# ProPrj__ByByte_Nano.net
KiCad netlist of a schematic drawn in EasyEDA Pro
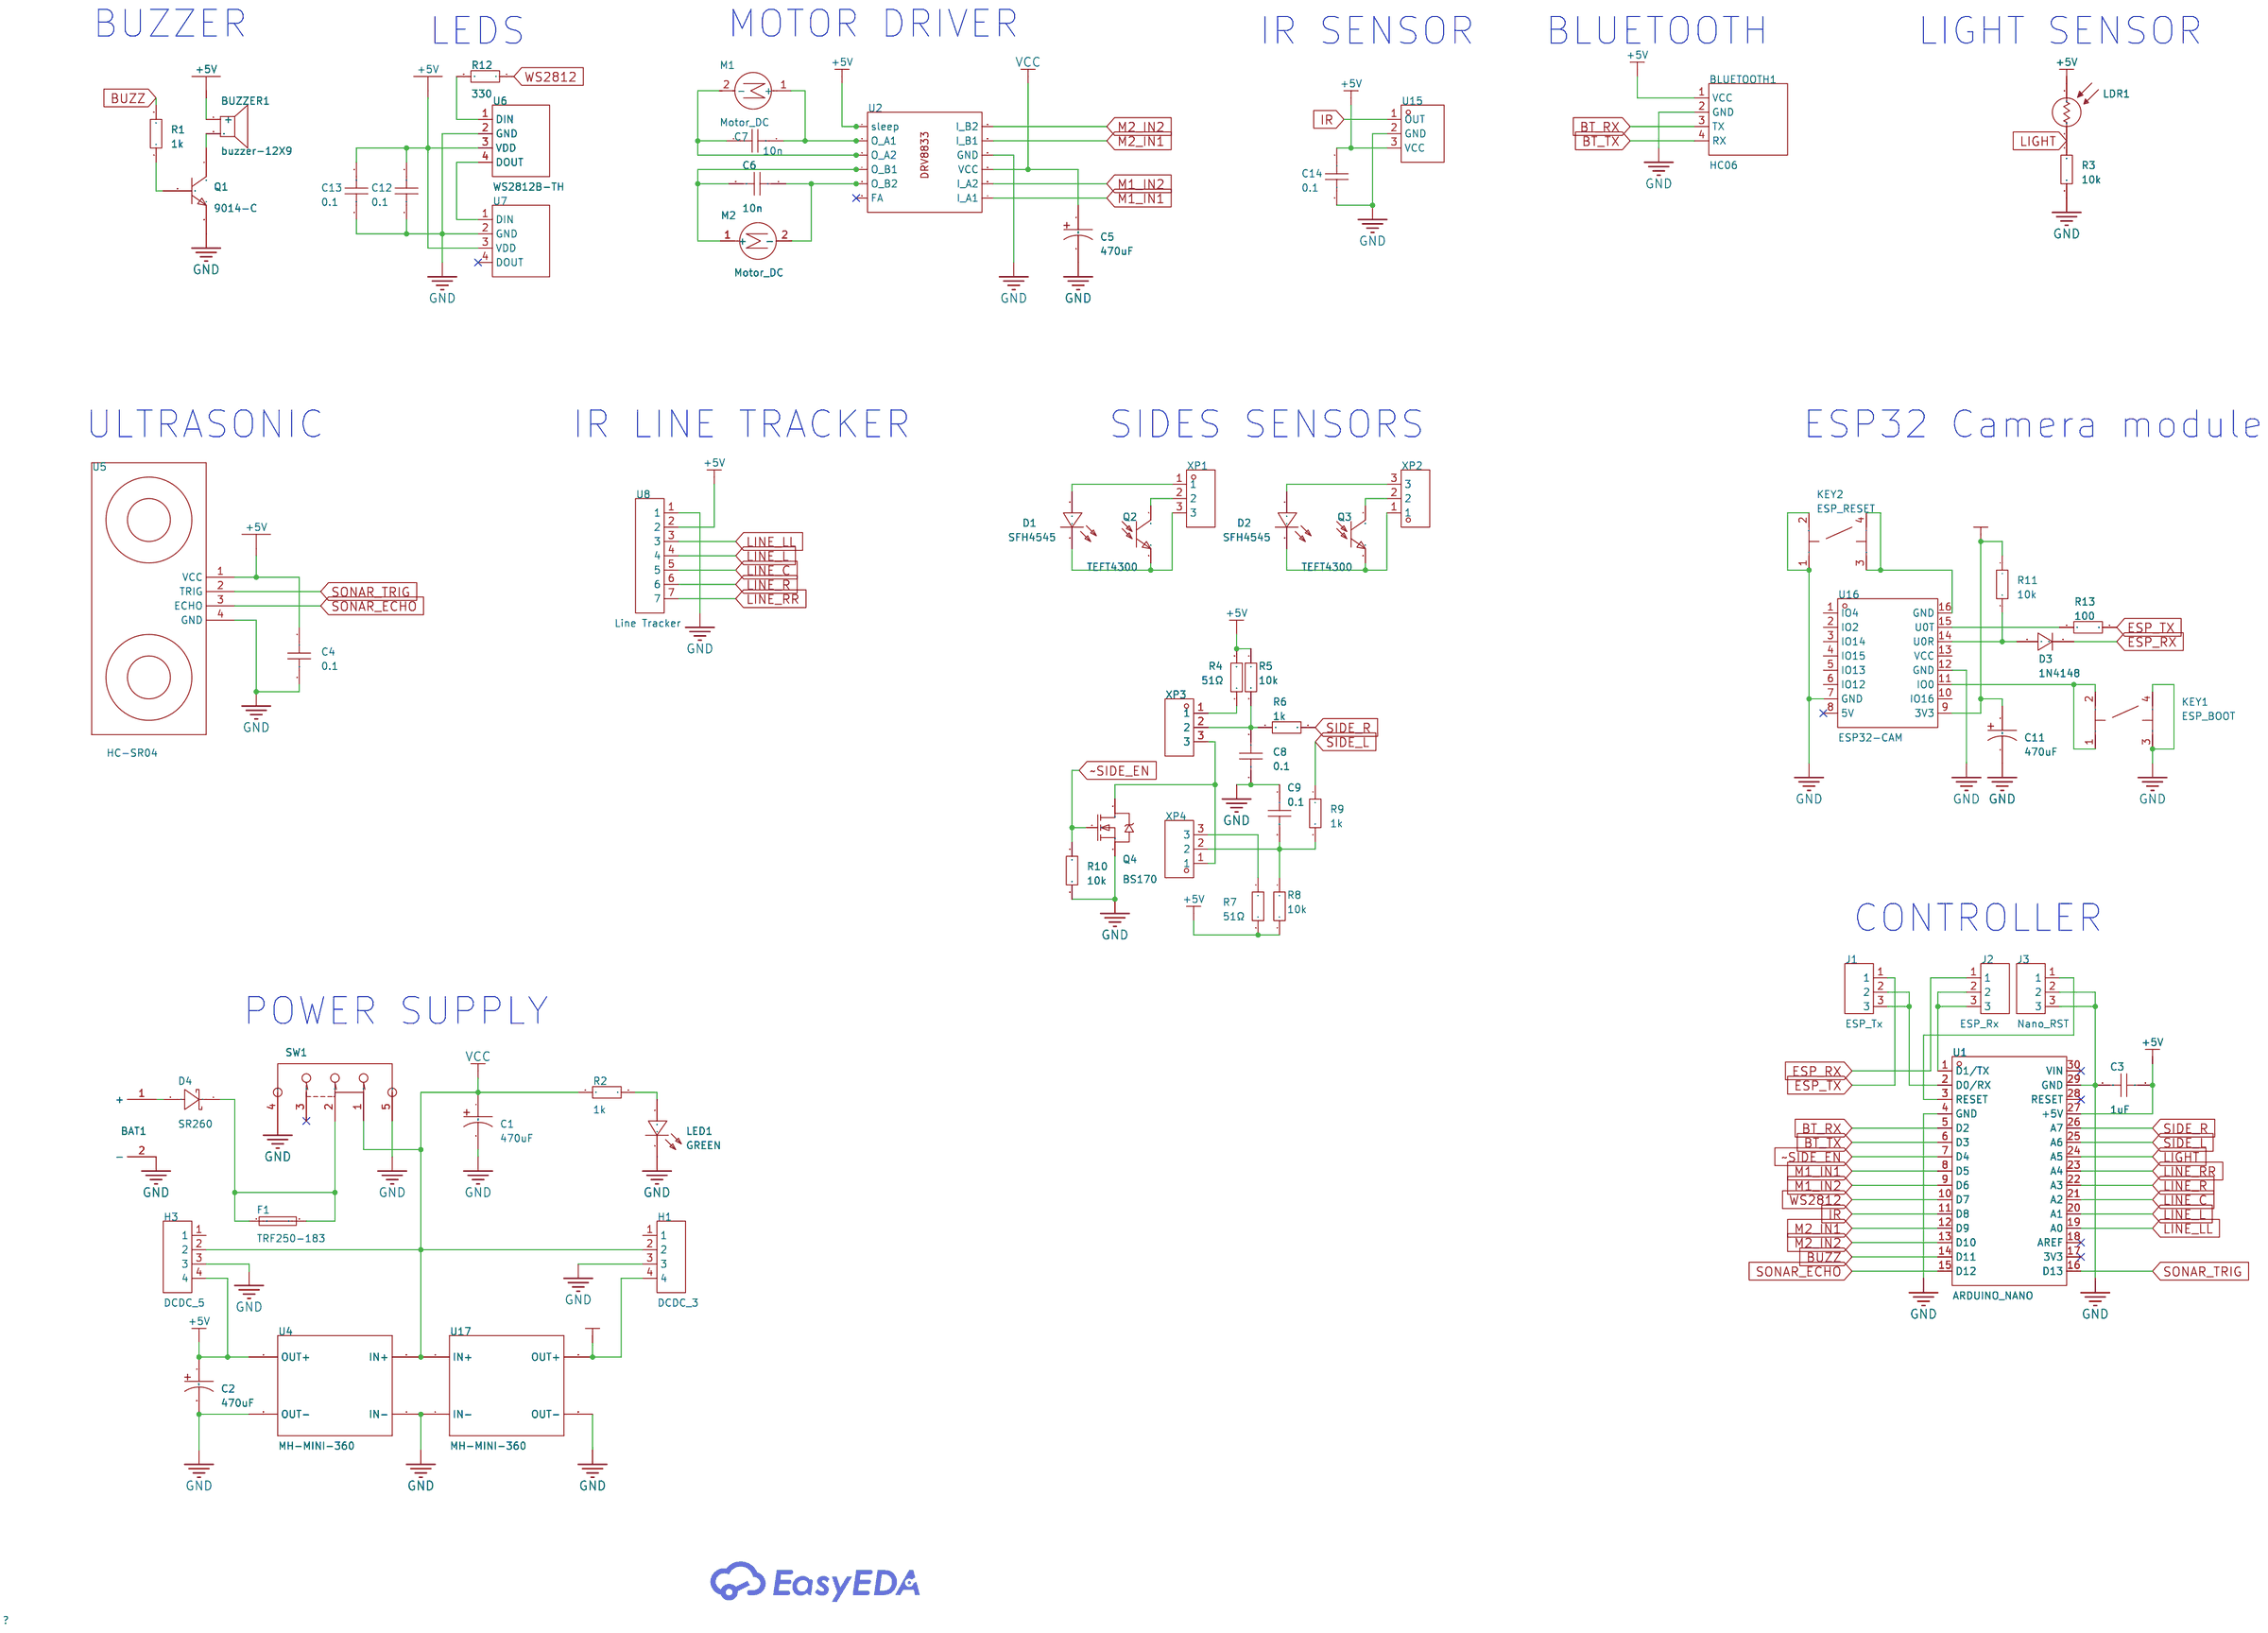
[diagram p0: schematic sheet]

(export (version "E")
  (design (tool "Eeschema 10.0.6"))
  (components
    (comp (ref "BAT1")
      (value "~")
      (footprint "easyedapro:9V BATTERY")
      (description "https://www.digikey.com/en/products/detail/mpd-memory-protection-devices/BH9VPC/31510")
      (libsource (lib "easyedapro") (part "BH9VPC"))
    )
    (comp (ref "BLUETOOTH1")
      (value "HC06")
      (footprint "easyedapro:HC06")
      (libsource (lib "easyedapro") (part "HC06"))
    )
    (comp (ref "BUZZER1")
      (value "buzzer-12X9")
      (footprint "easyedapro:BUZ-TH_BD12.0-P7.60-D0.6-FD")
      (libsource (lib "easyedapro") (part "BUZZER-12X9"))
    )
    (comp (ref "C1")
      (value "470uF")
      (footprint "easyedapro:CAP-TH_BD8.0-P3.50-D0.6-FD-2")
      (fields (field (name "Manufacturer Part") "RXW471M1CBK-0811") (field (name "Manufacturer") "Lelon(立隆)"))
      (libsource (lib "easyedapro") (part "RXW471M1CBK-0811"))
    )
    (comp (ref "C2")
      (value "470uF")
      (footprint "easyedapro:CAP-TH_BD8.0-P3.50-D0.6-FD-2")
      (fields (field (name "Manufacturer Part") "RXW471M1CBK-0811") (field (name "Manufacturer") "Lelon(立隆)"))
      (libsource (lib "easyedapro") (part "RXW471M1CBK-0811"))
    )
    (comp (ref "C3")
      (value "1uF")
      (footprint "easyedapro:CAP-TH_L4.0-W2.5-P2.50-D0.5")
      (fields (field (name "Manufacturer Part") "FK18X5R1C105K") (field (name "Manufacturer") "TDK"))
      (libsource (lib "easyedapro") (part "FK18X5R1C105K"))
    )
    (comp (ref "C4")
      (value "0.1")
      (footprint "easyedapro:CAP-TH_L4.0-W2.5-P2.50-D0.5")
      (fields (field (name "Manufacturer Part") "FK18X5R1C105K") (field (name "Manufacturer") "TDK"))
      (libsource (lib "easyedapro") (part "FK18X5R1C105K"))
    )
    (comp (ref "C5")
      (value "470uF")
      (footprint "easyedapro:CAP-TH_BD8.0-P3.50-D0.6-FD-2")
      (fields (field (name "Manufacturer Part") "RXW471M1CBK-0811") (field (name "Manufacturer") "Lelon(立隆)"))
      (libsource (lib "easyedapro") (part "RXW471M1CBK-0811"))
    )
    (comp (ref "C6")
      (value "10n")
      (footprint "easyedapro:CAP-TH_L4.0-W2.5-P2.50-D0.5")
      (fields (field (name "Manufacturer Part") "FK18X5R1C105K") (field (name "Manufacturer") "TDK"))
      (libsource (lib "easyedapro") (part "FK18X5R1C105K"))
    )
    (comp (ref "C7")
      (value "10n")
      (footprint "easyedapro:CAP-TH_L4.0-W2.5-P2.50-D0.5")
      (fields (field (name "Manufacturer Part") "FK18X5R1C105K") (field (name "Manufacturer") "TDK"))
      (libsource (lib "easyedapro") (part "FK18X5R1C105K"))
    )
    (comp (ref "C8")
      (value "0.1")
      (footprint "easyedapro:CAP-TH_L4.0-W2.5-P2.50-D0.5")
      (fields (field (name "Manufacturer Part") "FK18X5R1C105K") (field (name "Manufacturer") "TDK"))
      (libsource (lib "easyedapro") (part "FK18X5R1C105K"))
    )
    (comp (ref "C9")
      (value "0.1")
      (footprint "easyedapro:CAP-TH_L4.0-W2.5-P2.50-D0.5")
      (fields (field (name "Manufacturer Part") "FK18X5R1C105K") (field (name "Manufacturer") "TDK"))
      (libsource (lib "easyedapro") (part "FK18X5R1C105K"))
    )
    (comp (ref "C11")
      (value "470uF")
      (footprint "easyedapro:CAP-TH_BD8.0-P3.50-D0.6-FD-2")
      (fields (field (name "Manufacturer Part") "RXW471M1CBK-0811") (field (name "Manufacturer") "Lelon(立隆)"))
      (libsource (lib "easyedapro") (part "RXW471M1CBK-0811"))
    )
    (comp (ref "C12")
      (value "0.1")
      (footprint "easyedapro:CAP-TH_L4.0-W2.5-P2.50-D0.5")
      (fields (field (name "Manufacturer Part") "FK18X5R1C105K") (field (name "Manufacturer") "TDK"))
      (libsource (lib "easyedapro") (part "FK18X5R1C105K"))
    )
    (comp (ref "C13")
      (value "0.1")
      (footprint "easyedapro:CAP-TH_L4.0-W2.5-P2.50-D0.5")
      (fields (field (name "Manufacturer Part") "FK18X5R1C105K") (field (name "Manufacturer") "TDK"))
      (libsource (lib "easyedapro") (part "FK18X5R1C105K"))
    )
    (comp (ref "C14")
      (value "0.1")
      (footprint "easyedapro:CAP-TH_L4.0-W2.5-P2.50-D0.5")
      (fields (field (name "Manufacturer Part") "FK18X5R1C105K") (field (name "Manufacturer") "TDK"))
      (libsource (lib "easyedapro") (part "FK18X5R1C105K"))
    )
    (comp (ref "D1")
      (value "SFH4545")
      (footprint "easyedapro:LED-TH_BD5.0-P2.54-FD")
      (libsource (lib "easyedapro") (part "SFH4550"))
    )
    (comp (ref "D2")
      (value "SFH4545")
      (footprint "easyedapro:LED-TH_BD5.0-P2.54-FD")
      (libsource (lib "easyedapro") (part "SFH4550"))
    )
    (comp (ref "D3")
      (value "1N4148")
      (footprint "easyedapro:DO-35_BD2.0-L4.0-P8.0-D0.5-RD")
      (libsource (lib "easyedapro") (part "1N4148_C13769"))
    )
    (comp (ref "D4")
      (value "SR260")
      (footprint "easyedapro:DO-15_BD3.1-L6.7-P10.70-D0.9-RD")
      (fields (field (name "Manufacturer") "TF(拓锋)"))
      (libsource (lib "easyedapro") (part "SR260_C845406"))
    )
    (comp (ref "F1")
      (value "TRF250-183")
      (footprint "easyedapro:FUSE-TH_L7.5-W3.8-P5.00-D0.8")
      (fields (field (name "Manufacturer") "Littelfuse(美国力特)"))
      (libsource (lib "easyedapro") (part "TRF250-183"))
    )
    (comp (ref "H1")
      (value "DCDC_3")
      (footprint "easyedapro:HDR-TH_4P-P2.54-V-F")
      (libsource (lib "easyedapro") (part "HC-08蓝牙"))
    )
    (comp (ref "H3")
      (value "DCDC_5")
      (footprint "easyedapro:HDR-TH_4P-P2.54-V-F")
      (libsource (lib "easyedapro") (part "HC-08蓝牙"))
    )
    (comp (ref "J1")
      (value "ESP_Tx")
      (footprint "easyedapro:HDR-TH_3P-P2.54-V-M-A")
      (libsource (lib "easyedapro") (part "JUMPER3"))
    )
    (comp (ref "J2")
      (value "ESP_Rx")
      (footprint "easyedapro:HDR-TH_3P-P2.54-V-M-A")
      (libsource (lib "easyedapro") (part "JUMPER3"))
    )
    (comp (ref "J3")
      (value "Nano_RST")
      (footprint "easyedapro:HDR-TH_3P-P2.54-V-M-A")
      (libsource (lib "easyedapro") (part "JUMPER3"))
    )
    (comp (ref "KEY1")
      (value "ESP_BOOT")
      (footprint "easyedapro:KEY-TH_4P-L6.0-W6.0-P6.50-LS4.5")
      (libsource (lib "easyedapro") (part "AN6*6"))
    )
    (comp (ref "KEY2")
      (value "ESP_RESET")
      (footprint "easyedapro:KEY-TH_4P-L6.0-W6.0-P6.50-LS4.5")
      (libsource (lib "easyedapro") (part "AN6*6"))
    )
    (comp (ref "LDR1")
      (value "~")
      (footprint "easyedapro:PHOTO_RESISTOR")
      (libsource (lib "easyedapro") (part "Photo-Resistor"))
    )
    (comp (ref "LED1")
      (value "PWR")
      (footprint "easyedapro:LED-TH_BD3.0-P2.54-FD-GREEN")
      (fields (field (name "Manufacturer Part") "GREEN"))
      (libsource (lib "easyedapro") (part "插针式LEDF3_C9900017231"))
    )
    (comp (ref "M1") (value "Motor_DC") (libsource (lib "easyedapro") (part "Motor_DC")))
    (comp (ref "M2") (value "Motor_DC") (libsource (lib "easyedapro") (part "Motor_DC")))
    (comp (ref "Q1")
      (value "9014-C")
      (footprint "easyedapro:TO-92-3_L4.8-W3.7-P2.54-R")
      (fields (field (name "Manufacturer") "BLUE ROCKET(蓝箭)"))
      (libsource (lib "easyedapro") (part "9014-C"))
    )
    (comp (ref "Q2")
      (value "TEFT4300")
      (footprint "easyedapro:SENSOR-TH_TEFT4300")
      (fields (field (name "Manufacturer") "VISHAY(威世)"))
      (libsource (lib "easyedapro") (part "TEFT4300"))
    )
    (comp (ref "Q3")
      (value "TEFT4300")
      (footprint "easyedapro:SENSOR-TH_TEFT4300")
      (fields (field (name "Manufacturer") "VISHAY(威世)"))
      (libsource (lib "easyedapro") (part "TEFT4300"))
    )
    (comp (ref "Q4")
      (value "BS170")
      (footprint "easyedapro:TO-92-3_L4.8-W3.7-P2.54-L")
      (fields (field (name "Manufacturer") "onsemi(安森美)"))
      (libsource (lib "easyedapro") (part "BS170-D26Z"))
    )
    (comp (ref "R1")
      (value "1k")
      (footprint "easyedapro:R_AXIAL-0.4")
      (libsource (lib "easyedapro") (part "Res"))
    )
    (comp (ref "R2")
      (value "1k")
      (footprint "easyedapro:R_AXIAL-0.4")
      (libsource (lib "easyedapro") (part "Res"))
    )
    (comp (ref "R3")
      (value "10k")
      (footprint "easyedapro:R_AXIAL-0.4")
      (libsource (lib "easyedapro") (part "Res"))
    )
    (comp (ref "R4")
      (value "51Ω")
      (footprint "easyedapro:R_AXIAL-0.4")
      (libsource (lib "easyedapro") (part "Res"))
    )
    (comp (ref "R5")
      (value "10k")
      (footprint "easyedapro:R_AXIAL-0.4")
      (libsource (lib "easyedapro") (part "Res"))
    )
    (comp (ref "R6")
      (value "1k")
      (footprint "easyedapro:R_AXIAL-0.4")
      (libsource (lib "easyedapro") (part "Res"))
    )
    (comp (ref "R7")
      (value "51Ω")
      (footprint "easyedapro:R_AXIAL-0.4")
      (libsource (lib "easyedapro") (part "Res"))
    )
    (comp (ref "R8")
      (value "10k")
      (footprint "easyedapro:R_AXIAL-0.4")
      (libsource (lib "easyedapro") (part "Res"))
    )
    (comp (ref "R9")
      (value "1k")
      (footprint "easyedapro:R_AXIAL-0.4")
      (libsource (lib "easyedapro") (part "Res"))
    )
    (comp (ref "R10")
      (value "10k")
      (footprint "easyedapro:R_AXIAL-0.4")
      (libsource (lib "easyedapro") (part "Res"))
    )
    (comp (ref "R11")
      (value "10k")
      (footprint "easyedapro:R_AXIAL-0.4")
      (libsource (lib "easyedapro") (part "Res"))
    )
    (comp (ref "R12")
      (value "330")
      (footprint "easyedapro:R_AXIAL-0.4")
      (libsource (lib "easyedapro") (part "Res"))
    )
    (comp (ref "R13")
      (value "100")
      (footprint "easyedapro:R_AXIAL-0.4")
      (libsource (lib "easyedapro") (part "Res"))
    )
    (comp (ref "SW1")
      (value "SW-TH_HOOYA_SS-12D11G4")
      (footprint "easyedapro:SW-TH_HOOYA_SS-12D11G4")
      (libsource (lib "easyedapro") (part "SW-TH_HOOYA_SS-12D11G4"))
    )
    (comp (ref "U1")
      (value "ARDUINO_NANO")
      (footprint "easyedapro:COMM-TH_ARDUINO_NANO")
      (libsource (lib "easyedapro") (part "ARDUINO_NANO"))
    )
    (comp (ref "U2")
      (value "~")
      (footprint "easyedapro:DRV8833")
      (libsource (lib "easyedapro") (part "DRV8833"))
    )
    (comp (ref "U4")
      (value "MH-MINI-360")
      (footprint "easyedapro:DC-DC-STEP-DOWN-MP2307")
      (libsource (lib "easyedapro") (part "#promini_DC-DC-STEP-DOWN-MP2307_"))
    )
    (comp (ref "U5")
      (value "HC-SR04")
      (footprint "easyedapro:ULTRASONIC-HC-SR04#V")
      (libsource (lib "easyedapro") (part "ULTRASONIC-HC-SR04_#V"))
    )
    (comp (ref "U6")
      (value "WS2812B-TH")
      (footprint "easyedapro:LED-TH_4P-BD5.8_WS2812B-TH")
      (libsource (lib "easyedapro") (part "WS2812B-TH"))
    )
    (comp (ref "U7")
      (value "WS2812B-TH")
      (footprint "easyedapro:LED-TH_4P-BD5.8_WS2812B-TH")
      (libsource (lib "easyedapro") (part "WS2812B-TH"))
    )
    (comp (ref "U8")
      (value "Line Tracker")
      (footprint "easyedapro:HDR-TH_7P-P2.54-V-F")
      (fields (field (name "Manufacturer Part") "7位插座"))
      (libsource (lib "easyedapro") (part "7位插座"))
    )
    (comp (ref "U15")
      (value "D38")
      (footprint "easyedapro:OPTO-TH_VS1838B")
      (fields (field (name "Manufacturer Part") "VS1838B"))
      (libsource (lib "easyedapro") (part "VS1838B"))
    )
    (comp (ref "U16")
      (value "ESP32-CAM")
      (footprint "easyedapro:COMM-TH_16P-L40.0-W27.0-P2.54_ESP32-CAM")
      (description "ESP32-CAM_AI-THINKER")
      (fields (field (name "Manufacturer") "Ai-Thinker(安信可)"))
      (libsource (lib "easyedapro") (part "ESP32-CAM"))
    )
    (comp (ref "U17")
      (value "MH-MINI-360")
      (footprint "easyedapro:DC-DC-STEP-DOWN-MP2307")
      (libsource (lib "easyedapro") (part "#promini_DC-DC-STEP-DOWN-MP2307_"))
    )
    (comp (ref "XP1")
      (value "D32")
      (footprint "easyedapro:HDR-TH_3P-P2.54-V-M")
      (fields
        (field (name "Manufacturer Part") "5-146277-3")
        (field (name "Manufacturer") "TE Connectivity(泰科电子)")
      )
      (libsource (lib "easyedapro") (part "5-146277-3"))
    )
    (comp (ref "XP2")
      (value "D32")
      (footprint "easyedapro:HDR-TH_3P-P2.54-V-M")
      (fields
        (field (name "Manufacturer Part") "5-146277-3")
        (field (name "Manufacturer") "TE Connectivity(泰科电子)")
      )
      (libsource (lib "easyedapro") (part "5-146277-3"))
    )
    (comp (ref "XP3")
      (value "D32")
      (footprint "easyedapro:HDR-TH_3P-P2.54-V-M")
      (fields
        (field (name "Manufacturer Part") "5-146277-3")
        (field (name "Manufacturer") "TE Connectivity(泰科电子)")
      )
      (libsource (lib "easyedapro") (part "5-146277-3"))
    )
    (comp (ref "XP4")
      (value "D32")
      (footprint "easyedapro:HDR-TH_3P-P2.54-V-M")
      (fields
        (field (name "Manufacturer Part") "5-146277-3")
        (field (name "Manufacturer") "TE Connectivity(泰科电子)")
      )
      (libsource (lib "easyedapro") (part "5-146277-3"))
    )
  )
  (nets
    (net (code "1") (name "+3.3V") (class "Default")
      (node (ref "C11") (pin "1") (pinfunction "1_1") (pintype "unspecified"))
      (node (ref "H1") (pin "4") (pinfunction "4_4") (pintype "unspecified"))
      (node (ref "R11") (pin "1") (pinfunction "1_1") (pintype "input"))
      (node (ref "U16") (pin "9") (pinfunction "3V3_9") (pintype "unspecified"))
      (node (ref "U17") (pin "OUT+") (pinfunction "OUT+_OUT+") (pintype "bidirectional"))
    )
    (net (code "2") (name "+5V") (class "Default")
      (node (ref "BLUETOOTH1") (pin "1") (pinfunction "VCC_1") (pintype "input"))
      (node (ref "BUZZER1") (pin "1") (pinfunction "+_1") (pintype "input"))
      (node (ref "C12") (pin "1") (pinfunction "1_1") (pintype "unspecified"))
      (node (ref "C13") (pin "1") (pinfunction "1_1") (pintype "unspecified"))
      (node (ref "C14") (pin "1") (pinfunction "1_1") (pintype "unspecified"))
      (node (ref "C2") (pin "1") (pinfunction "1_1") (pintype "unspecified"))
      (node (ref "C3") (pin "2") (pinfunction "2_2") (pintype "unspecified"))
      (node (ref "C4") (pin "1") (pinfunction "1_1") (pintype "unspecified"))
      (node (ref "H3") (pin "4") (pinfunction "4_4") (pintype "unspecified"))
      (node (ref "LDR1") (pin "1") (pinfunction "1_1") (pintype "unspecified"))
      (node (ref "R4") (pin "2") (pinfunction "2_2") (pintype "input"))
      (node (ref "R5") (pin "1") (pinfunction "1_1") (pintype "input"))
      (node (ref "R7") (pin "2") (pinfunction "2_2") (pintype "input"))
      (node (ref "R8") (pin "2") (pinfunction "2_2") (pintype "input"))
      (node (ref "U1") (pin "27") (pinfunction "+5V_27") (pintype "unspecified"))
      (node (ref "U15") (pin "3") (pinfunction "VCC_3") (pintype "unspecified"))
      (node (ref "U2") (pin "1") (pinfunction "sleep_1") (pintype "input"))
      (node (ref "U4") (pin "OUT+") (pinfunction "OUT+_OUT+") (pintype "bidirectional"))
      (node (ref "U5") (pin "1") (pinfunction "VCC_1") (pintype "input"))
      (node (ref "U6") (pin "3") (pinfunction "VDD_3") (pintype "unspecified"))
      (node (ref "U7") (pin "3") (pinfunction "VDD_3") (pintype "unspecified"))
      (node (ref "U8") (pin "2") (pinfunction "2_2") (pintype "unspecified"))
    )
    (net (code "3") (name "BT_RX") (class "Default")
      (node (ref "BLUETOOTH1") (pin "3") (pinfunction "TX_3") (pintype "input"))
      (node (ref "U1") (pin "5") (pinfunction "D2_5") (pintype "unspecified"))
    )
    (net (code "4") (name "BT_TX") (class "Default")
      (node (ref "BLUETOOTH1") (pin "4") (pinfunction "RX_4") (pintype "input"))
      (node (ref "U1") (pin "6") (pinfunction "D3_6") (pintype "unspecified"))
    )
    (net (code "5") (name "BUZZ") (class "Default")
      (node (ref "R1") (pin "2") (pinfunction "2_2") (pintype "input"))
      (node (ref "U1") (pin "14") (pinfunction "D11_14") (pintype "unspecified"))
    )
    (net (code "6") (name "ESP_RX") (class "Default")
      (node (ref "D3") (pin "1") (pinfunction "1_1") (pintype "unspecified"))
      (node (ref "J2") (pin "1") (pinfunction "1_1") (pintype "unspecified"))
    )
    (net (code "7") (name "ESP_TX") (class "Default")
      (node (ref "J1") (pin "1") (pinfunction "1_1") (pintype "unspecified"))
      (node (ref "R13") (pin "2") (pinfunction "2_2") (pintype "input"))
    )
    (net (code "8") (name "GND") (class "Default")
      (node (ref "BAT1") (pin "2") (pinfunction "-_2") (pintype "input"))
      (node (ref "BLUETOOTH1") (pin "2") (pinfunction "GND_2") (pintype "input"))
      (node (ref "C1") (pin "2") (pinfunction "2_2") (pintype "unspecified"))
      (node (ref "C11") (pin "2") (pinfunction "2_2") (pintype "unspecified"))
      (node (ref "C12") (pin "2") (pinfunction "2_2") (pintype "unspecified"))
      (node (ref "C13") (pin "2") (pinfunction "2_2") (pintype "unspecified"))
      (node (ref "C14") (pin "2") (pinfunction "2_2") (pintype "unspecified"))
      (node (ref "C2") (pin "2") (pinfunction "2_2") (pintype "unspecified"))
      (node (ref "C3") (pin "1") (pinfunction "1_1") (pintype "unspecified"))
      (node (ref "C4") (pin "2") (pinfunction "2_2") (pintype "unspecified"))
      (node (ref "C5") (pin "2") (pinfunction "2_2") (pintype "unspecified"))
      (node (ref "C8") (pin "1") (pinfunction "1_1") (pintype "unspecified"))
      (node (ref "C9") (pin "1") (pinfunction "1_1") (pintype "unspecified"))
      (node (ref "H1") (pin "3") (pinfunction "3_3") (pintype "unspecified"))
      (node (ref "H3") (pin "3") (pinfunction "3_3") (pintype "unspecified"))
      (node (ref "J3") (pin "2") (pinfunction "2_2") (pintype "unspecified"))
      (node (ref "J3") (pin "3") (pinfunction "3_3") (pintype "unspecified"))
      (node (ref "KEY1") (pin "3") (pinfunction "3_3") (pintype "unspecified"))
      (node (ref "KEY1") (pin "4") (pinfunction "4_4") (pintype "unspecified"))
      (node (ref "KEY2") (pin "1") (pinfunction "1_1") (pintype "unspecified"))
      (node (ref "KEY2") (pin "2") (pinfunction "2_2") (pintype "unspecified"))
      (node (ref "LED1") (pin "2") (pinfunction "K_2") (pintype "unspecified"))
      (node (ref "Q1") (pin "3") (pinfunction "E_3") (pintype "unspecified"))
      (node (ref "Q4") (pin "3") (pinfunction "S_3") (pintype "unspecified"))
      (node (ref "R10") (pin "2") (pinfunction "2_2") (pintype "input"))
      (node (ref "R3") (pin "1") (pinfunction "1_1") (pintype "input"))
      (node (ref "SW1") (pin "4") (pinfunction "4_4") (pintype "unspecified"))
      (node (ref "SW1") (pin "5") (pinfunction "5_5") (pintype "unspecified"))
      (node (ref "U1") (pin "29") (pinfunction "GND_29") (pintype "unspecified"))
      (node (ref "U1") (pin "4") (pinfunction "GND_4") (pintype "unspecified"))
      (node (ref "U15") (pin "2") (pinfunction "GND_2") (pintype "unspecified"))
      (node (ref "U16") (pin "12") (pinfunction "GND_12") (pintype "unspecified"))
      (node (ref "U16") (pin "7") (pinfunction "GND_7") (pintype "unspecified"))
      (node (ref "U17") (pin "IN-") (pinfunction "IN-_IN-") (pintype "bidirectional"))
      (node (ref "U17") (pin "OUT-") (pinfunction "OUT-_OUT-") (pintype "bidirectional"))
      (node (ref "U2") (pin "10") (pinfunction "GND_10") (pintype "input"))
      (node (ref "U4") (pin "IN-") (pinfunction "IN-_IN-") (pintype "bidirectional"))
      (node (ref "U4") (pin "OUT-") (pinfunction "OUT-_OUT-") (pintype "bidirectional"))
      (node (ref "U5") (pin "4") (pinfunction "GND_4") (pintype "input"))
      (node (ref "U6") (pin "2") (pinfunction "GND_2") (pintype "unspecified"))
      (node (ref "U7") (pin "2") (pinfunction "GND_2") (pintype "unspecified"))
      (node (ref "U8") (pin "1") (pinfunction "1_1") (pintype "unspecified"))
    )
    (net (code "9") (name "IR") (class "Default")
      (node (ref "U1") (pin "11") (pinfunction "D8_11") (pintype "unspecified"))
      (node (ref "U15") (pin "1") (pinfunction "OUT_1") (pintype "unspecified"))
    )
    (net (code "10") (name "LIGHT") (class "Default")
      (node (ref "LDR1") (pin "2") (pinfunction "2_2") (pintype "unspecified"))
      (node (ref "R3") (pin "2") (pinfunction "2_2") (pintype "input"))
      (node (ref "U1") (pin "24") (pinfunction "A5_24") (pintype "unspecified"))
    )
    (net (code "11") (name "LINE_C") (class "Default")
      (node (ref "U1") (pin "21") (pinfunction "A2_21") (pintype "unspecified"))
      (node (ref "U8") (pin "5") (pinfunction "5_5") (pintype "unspecified"))
    )
    (net (code "12") (name "LINE_L") (class "Default")
      (node (ref "U1") (pin "20") (pinfunction "A1_20") (pintype "unspecified"))
      (node (ref "U8") (pin "4") (pinfunction "4_4") (pintype "unspecified"))
    )
    (net (code "13") (name "LINE_LL") (class "Default")
      (node (ref "U1") (pin "19") (pinfunction "A0_19") (pintype "unspecified"))
      (node (ref "U8") (pin "3") (pinfunction "3_3") (pintype "unspecified"))
    )
    (net (code "14") (name "LINE_R") (class "Default")
      (node (ref "U1") (pin "22") (pinfunction "A3_22") (pintype "unspecified"))
      (node (ref "U8") (pin "6") (pinfunction "6_6") (pintype "unspecified"))
    )
    (net (code "15") (name "LINE_RR") (class "Default")
      (node (ref "U1") (pin "23") (pinfunction "A4_23") (pintype "unspecified"))
      (node (ref "U8") (pin "7") (pinfunction "7_7") (pintype "unspecified"))
    )
    (net (code "16") (name "M1_IN1") (class "Default")
      (node (ref "U1") (pin "8") (pinfunction "D5_8") (pintype "unspecified"))
      (node (ref "U2") (pin "7") (pinfunction "I_A1_7") (pintype "input"))
    )
    (net (code "17") (name "M1_IN2") (class "Default")
      (node (ref "U1") (pin "9") (pinfunction "D6_9") (pintype "unspecified"))
      (node (ref "U2") (pin "8") (pinfunction "I_A2_8") (pintype "input"))
    )
    (net (code "18") (name "M2_IN1") (class "Default")
      (node (ref "U1") (pin "12") (pinfunction "D9_12") (pintype "unspecified"))
      (node (ref "U2") (pin "11") (pinfunction "I_B1_11") (pintype "input"))
    )
    (net (code "19") (name "M2_IN2") (class "Default")
      (node (ref "U1") (pin "13") (pinfunction "D10_13") (pintype "unspecified"))
      (node (ref "U2") (pin "12") (pinfunction "I_B2_12") (pintype "input"))
    )
    (net (code "20") (name "Net-(BAT1-+)") (class "Default")
      (node (ref "BAT1") (pin "1") (pinfunction "+_1") (pintype "input"))
      (node (ref "D4") (pin "2") (pinfunction "A_2") (pintype "unspecified"))
    )
    (net (code "21") (name "Net-(C8-Pad2)") (class "Default")
      (node (ref "C8") (pin "2") (pinfunction "2_2") (pintype "unspecified"))
      (node (ref "R5") (pin "2") (pinfunction "2_2") (pintype "input"))
      (node (ref "R6") (pin "2") (pinfunction "2_2") (pintype "input"))
      (node (ref "XP3") (pin "2") (pinfunction "2_2") (pintype "unspecified"))
    )
    (net (code "22") (name "Net-(C9-Pad2)") (class "Default")
      (node (ref "C9") (pin "2") (pinfunction "2_2") (pintype "unspecified"))
      (node (ref "R8") (pin "1") (pinfunction "1_1") (pintype "input"))
      (node (ref "R9") (pin "2") (pinfunction "2_2") (pintype "input"))
      (node (ref "XP4") (pin "2") (pinfunction "2_2") (pintype "unspecified"))
    )
    (net (code "23") (name "Net-(D1-A)") (class "Default")
      (node (ref "D1") (pin "1") (pinfunction "A_1") (pintype "unspecified"))
      (node (ref "XP1") (pin "1") (pinfunction "1_1") (pintype "unspecified"))
    )
    (net (code "24") (name "Net-(D1-K)") (class "Default")
      (node (ref "D1") (pin "2") (pinfunction "K_2") (pintype "unspecified"))
      (node (ref "Q2") (pin "2") (pinfunction "E_2") (pintype "input"))
      (node (ref "XP1") (pin "3") (pinfunction "3_3") (pintype "unspecified"))
    )
    (net (code "25") (name "Net-(D2-A)") (class "Default")
      (node (ref "D2") (pin "1") (pinfunction "A_1") (pintype "unspecified"))
      (node (ref "XP2") (pin "3") (pinfunction "3_3") (pintype "unspecified"))
    )
    (net (code "26") (name "Net-(D2-K)") (class "Default")
      (node (ref "D2") (pin "2") (pinfunction "K_2") (pintype "unspecified"))
      (node (ref "Q3") (pin "2") (pinfunction "E_2") (pintype "input"))
      (node (ref "XP2") (pin "1") (pinfunction "1_1") (pintype "unspecified"))
    )
    (net (code "27") (name "Net-(D4-K)") (class "Default")
      (node (ref "D4") (pin "1") (pinfunction "K_1") (pintype "unspecified"))
      (node (ref "F1") (pin "1") (pinfunction "1_1") (pintype "input"))
      (node (ref "F1") (pin "2") (pinfunction "2_2") (pintype "input"))
      (node (ref "SW1") (pin "2") (pinfunction "2_2") (pintype "unspecified"))
    )
    (net (code "28") (name "Net-(J3-Pad1)") (class "Default")
      (node (ref "J3") (pin "1") (pinfunction "1_1") (pintype "unspecified"))
      (node (ref "U1") (pin "3") (pinfunction "RESET_3") (pintype "unspecified"))
    )
    (net (code "29") (name "Net-(KEY2-Pad3)") (class "Default")
      (node (ref "KEY2") (pin "3") (pinfunction "3_3") (pintype "unspecified"))
      (node (ref "KEY2") (pin "4") (pinfunction "4_4") (pintype "unspecified"))
      (node (ref "U16") (pin "16") (pinfunction "GND_16") (pintype "unspecified"))
    )
    (net (code "30") (name "Net-(LED1-A)") (class "Default")
      (node (ref "LED1") (pin "1") (pinfunction "A_1") (pintype "unspecified"))
      (node (ref "R2") (pin "1") (pinfunction "1_1") (pintype "input"))
    )
    (net (code "31") (name "Net-(M1-+)") (class "Default")
      (node (ref "C7") (pin "2") (pinfunction "2_2") (pintype "unspecified"))
      (node (ref "M1") (pin "1") (pinfunction "+_1") (pintype "input"))
      (node (ref "U2") (pin "2") (pinfunction "O_A1_2") (pintype "input"))
    )
    (net (code "32") (name "Net-(M1--)") (class "Default")
      (node (ref "C7") (pin "1") (pinfunction "1_1") (pintype "unspecified"))
      (node (ref "M1") (pin "2") (pinfunction "-_2") (pintype "input"))
      (node (ref "U2") (pin "3") (pinfunction "O_A2_3") (pintype "input"))
    )
    (net (code "33") (name "Net-(M2-+)") (class "Default")
      (node (ref "C6") (pin "2") (pinfunction "2_2") (pintype "unspecified"))
      (node (ref "M2") (pin "1") (pinfunction "+_1") (pintype "input"))
      (node (ref "U2") (pin "4") (pinfunction "O_B1_4") (pintype "input"))
    )
    (net (code "34") (name "Net-(M2--)") (class "Default")
      (node (ref "C6") (pin "1") (pinfunction "1_1") (pintype "unspecified"))
      (node (ref "M2") (pin "2") (pinfunction "-_2") (pintype "input"))
      (node (ref "U2") (pin "5") (pinfunction "O_B2_5") (pintype "input"))
    )
    (net (code "35") (name "Net-(Q1-B)") (class "Default")
      (node (ref "Q1") (pin "2") (pinfunction "B_2") (pintype "unspecified"))
      (node (ref "R1") (pin "1") (pinfunction "1_1") (pintype "input"))
    )
    (net (code "36") (name "Net-(Q1-C)") (class "Default")
      (node (ref "BUZZER1") (pin "2") (pinfunction "2_2") (pintype "input"))
      (node (ref "Q1") (pin "1") (pinfunction "C_1") (pintype "unspecified"))
    )
    (net (code "37") (name "Net-(Q2-C)") (class "Default")
      (node (ref "Q2") (pin "1") (pinfunction "C_1") (pintype "input"))
      (node (ref "XP1") (pin "2") (pinfunction "2_2") (pintype "unspecified"))
    )
    (net (code "38") (name "Net-(Q3-C)") (class "Default")
      (node (ref "Q3") (pin "1") (pinfunction "C_1") (pintype "input"))
      (node (ref "XP2") (pin "2") (pinfunction "2_2") (pintype "unspecified"))
    )
    (net (code "39") (name "Net-(Q4-D)") (class "Default")
      (node (ref "Q4") (pin "1") (pinfunction "D_1") (pintype "unspecified"))
      (node (ref "XP3") (pin "3") (pinfunction "3_3") (pintype "unspecified"))
      (node (ref "XP4") (pin "1") (pinfunction "1_1") (pintype "unspecified"))
    )
    (net (code "40") (name "Net-(R4-Pad1)") (class "Default")
      (node (ref "R4") (pin "1") (pinfunction "1_1") (pintype "input"))
      (node (ref "XP3") (pin "1") (pinfunction "1_1") (pintype "unspecified"))
    )
    (net (code "41") (name "Net-(R7-Pad1)") (class "Default")
      (node (ref "R7") (pin "1") (pinfunction "1_1") (pintype "input"))
      (node (ref "XP4") (pin "3") (pinfunction "3_3") (pintype "unspecified"))
    )
    (net (code "42") (name "Net-(U1-D0{slash}RX)") (class "Default")
      (node (ref "J1") (pin "2") (pinfunction "2_2") (pintype "unspecified"))
      (node (ref "J1") (pin "3") (pinfunction "3_3") (pintype "unspecified"))
      (node (ref "U1") (pin "2") (pinfunction "D0/RX_2") (pintype "unspecified"))
    )
    (net (code "43") (name "Net-(U1-D1{slash}TX)") (class "Default")
      (node (ref "J2") (pin "2") (pinfunction "2_2") (pintype "unspecified"))
      (node (ref "J2") (pin "3") (pinfunction "3_3") (pintype "unspecified"))
      (node (ref "U1") (pin "1") (pinfunction "D1/TX_1") (pintype "unspecified"))
    )
    (net (code "44") (name "Net-(U6-DIN)") (class "Default")
      (node (ref "R12") (pin "2") (pinfunction "2_2") (pintype "input"))
      (node (ref "U6") (pin "1") (pinfunction "DIN_1") (pintype "unspecified"))
    )
    (net (code "45") (name "Net-(U6-DOUT)") (class "Default")
      (node (ref "U6") (pin "4") (pinfunction "DOUT_4") (pintype "unspecified"))
      (node (ref "U7") (pin "1") (pinfunction "DIN_1") (pintype "unspecified"))
    )
    (net (code "46") (name "Net-(U16-IO0)") (class "Default")
      (node (ref "KEY1") (pin "1") (pinfunction "1_1") (pintype "unspecified"))
      (node (ref "KEY1") (pin "2") (pinfunction "2_2") (pintype "unspecified"))
      (node (ref "U16") (pin "11") (pinfunction "IO0_11") (pintype "unspecified"))
    )
    (net (code "47") (name "Net-(U16-U0R)") (class "Default")
      (node (ref "D3") (pin "2") (pinfunction "2_2") (pintype "unspecified"))
      (node (ref "R11") (pin "2") (pinfunction "2_2") (pintype "input"))
      (node (ref "U16") (pin "14") (pinfunction "U0R_14") (pintype "unspecified"))
    )
    (net (code "48") (name "Net-(U16-U0T)") (class "Default")
      (node (ref "R13") (pin "1") (pinfunction "1_1") (pintype "input"))
      (node (ref "U16") (pin "15") (pinfunction "U0T_15") (pintype "unspecified"))
    )
    (net (code "49") (name "SIDE_L") (class "Default")
      (node (ref "R9") (pin "1") (pinfunction "1_1") (pintype "input"))
      (node (ref "U1") (pin "25") (pinfunction "A6_25") (pintype "unspecified"))
    )
    (net (code "50") (name "SIDE_R") (class "Default")
      (node (ref "R6") (pin "1") (pinfunction "1_1") (pintype "input"))
      (node (ref "U1") (pin "26") (pinfunction "A7_26") (pintype "unspecified"))
    )
    (net (code "51") (name "SONAR_ECHO") (class "Default")
      (node (ref "U1") (pin "15") (pinfunction "D12_15") (pintype "unspecified"))
      (node (ref "U5") (pin "3") (pinfunction "ECHO_3") (pintype "output"))
    )
    (net (code "52") (name "SONAR_TRIG") (class "Default")
      (node (ref "U1") (pin "16") (pinfunction "D13_16") (pintype "unspecified"))
      (node (ref "U5") (pin "2") (pinfunction "TRIG_2") (pintype "input"))
    )
    (net (code "53") (name "VCC") (class "Default")
      (node (ref "C1") (pin "1") (pinfunction "1_1") (pintype "unspecified"))
      (node (ref "C5") (pin "1") (pinfunction "1_1") (pintype "unspecified"))
      (node (ref "H1") (pin "2") (pinfunction "2_2") (pintype "unspecified"))
      (node (ref "H3") (pin "2") (pinfunction "2_2") (pintype "unspecified"))
      (node (ref "R2") (pin "2") (pinfunction "2_2") (pintype "input"))
      (node (ref "SW1") (pin "1") (pinfunction "1_1") (pintype "unspecified"))
      (node (ref "U17") (pin "IN+") (pinfunction "IN+_IN+") (pintype "bidirectional"))
      (node (ref "U2") (pin "9") (pinfunction "VCC_9") (pintype "input"))
      (node (ref "U4") (pin "IN+") (pinfunction "IN+_IN+") (pintype "bidirectional"))
    )
    (net (code "54") (name "WS2812") (class "Default")
      (node (ref "R12") (pin "1") (pinfunction "1_1") (pintype "input"))
      (node (ref "U1") (pin "10") (pinfunction "D7_10") (pintype "unspecified"))
    )
    (net (code "55") (name "unconnected-(H1-Pad1)") (class "Default")
      (node (ref "H1") (pin "1") (pinfunction "1_1") (pintype "unspecified"))
    )
    (net (code "56") (name "unconnected-(H3-Pad1)") (class "Default")
      (node (ref "H3") (pin "1") (pinfunction "1_1") (pintype "unspecified"))
    )
    (net (code "57") (name "unconnected-(SW1-Pad3)") (class "Default")
      (node (ref "SW1") (pin "3") (pinfunction "3_3") (pintype "unspecified+no_connect"))
    )
    (net (code "58") (name "unconnected-(U1-3V3-Pad17)") (class "Default")
      (node (ref "U1") (pin "17") (pinfunction "3V3_17") (pintype "unspecified+no_connect"))
    )
    (net (code "59") (name "unconnected-(U1-AREF-Pad18)") (class "Default")
      (node (ref "U1") (pin "18") (pinfunction "AREF_18") (pintype "unspecified+no_connect"))
    )
    (net (code "60") (name "unconnected-(U1-RESET-Pad28)") (class "Default")
      (node (ref "U1") (pin "28") (pinfunction "RESET_28") (pintype "unspecified+no_connect"))
    )
    (net (code "61") (name "unconnected-(U1-VIN-Pad30)") (class "Default")
      (node (ref "U1") (pin "30") (pinfunction "VIN_30") (pintype "unspecified+no_connect"))
    )
    (net (code "62") (name "unconnected-(U2-FA-Pad6)") (class "Default")
      (node (ref "U2") (pin "6") (pinfunction "FA_6") (pintype "input+no_connect"))
    )
    (net (code "63") (name "unconnected-(U7-DOUT-Pad4)") (class "Default")
      (node (ref "U7") (pin "4") (pinfunction "DOUT_4") (pintype "unspecified+no_connect"))
    )
    (net (code "64") (name "unconnected-(U16-5V-Pad8)") (class "Default")
      (node (ref "U16") (pin "8") (pinfunction "5V_8") (pintype "unspecified+no_connect"))
    )
    (net (code "65") (name "unconnected-(U16-IO2-Pad2)") (class "Default")
      (node (ref "U16") (pin "2") (pinfunction "IO2_2") (pintype "unspecified"))
    )
    (net (code "66") (name "unconnected-(U16-IO4-Pad1)") (class "Default")
      (node (ref "U16") (pin "1") (pinfunction "IO4_1") (pintype "unspecified"))
    )
    (net (code "67") (name "unconnected-(U16-IO12-Pad6)") (class "Default")
      (node (ref "U16") (pin "6") (pinfunction "IO12_6") (pintype "unspecified"))
    )
    (net (code "68") (name "unconnected-(U16-IO13-Pad5)") (class "Default")
      (node (ref "U16") (pin "5") (pinfunction "IO13_5") (pintype "unspecified"))
    )
    (net (code "69") (name "unconnected-(U16-IO14-Pad3)") (class "Default")
      (node (ref "U16") (pin "3") (pinfunction "IO14_3") (pintype "unspecified"))
    )
    (net (code "70") (name "unconnected-(U16-IO15-Pad4)") (class "Default")
      (node (ref "U16") (pin "4") (pinfunction "IO15_4") (pintype "unspecified"))
    )
    (net (code "71") (name "unconnected-(U16-IO16-Pad10)") (class "Default")
      (node (ref "U16") (pin "10") (pinfunction "IO16_10") (pintype "unspecified"))
    )
    (net (code "72") (name "unconnected-(U16-VCC-Pad13)") (class "Default")
      (node (ref "U16") (pin "13") (pinfunction "VCC_13") (pintype "unspecified"))
    )
    (net (code "73") (name "~SIDE_EN") (class "Default")
      (node (ref "Q4") (pin "2") (pinfunction "G_2") (pintype "unspecified"))
      (node (ref "R10") (pin "1") (pinfunction "1_1") (pintype "input"))
      (node (ref "U1") (pin "7") (pinfunction "D4_7") (pintype "unspecified"))
    )
  )
)
